# SCH_Vertical-Carousel_2025-01-21.net
KiCad netlist of a schematic drawn in EasyEDA
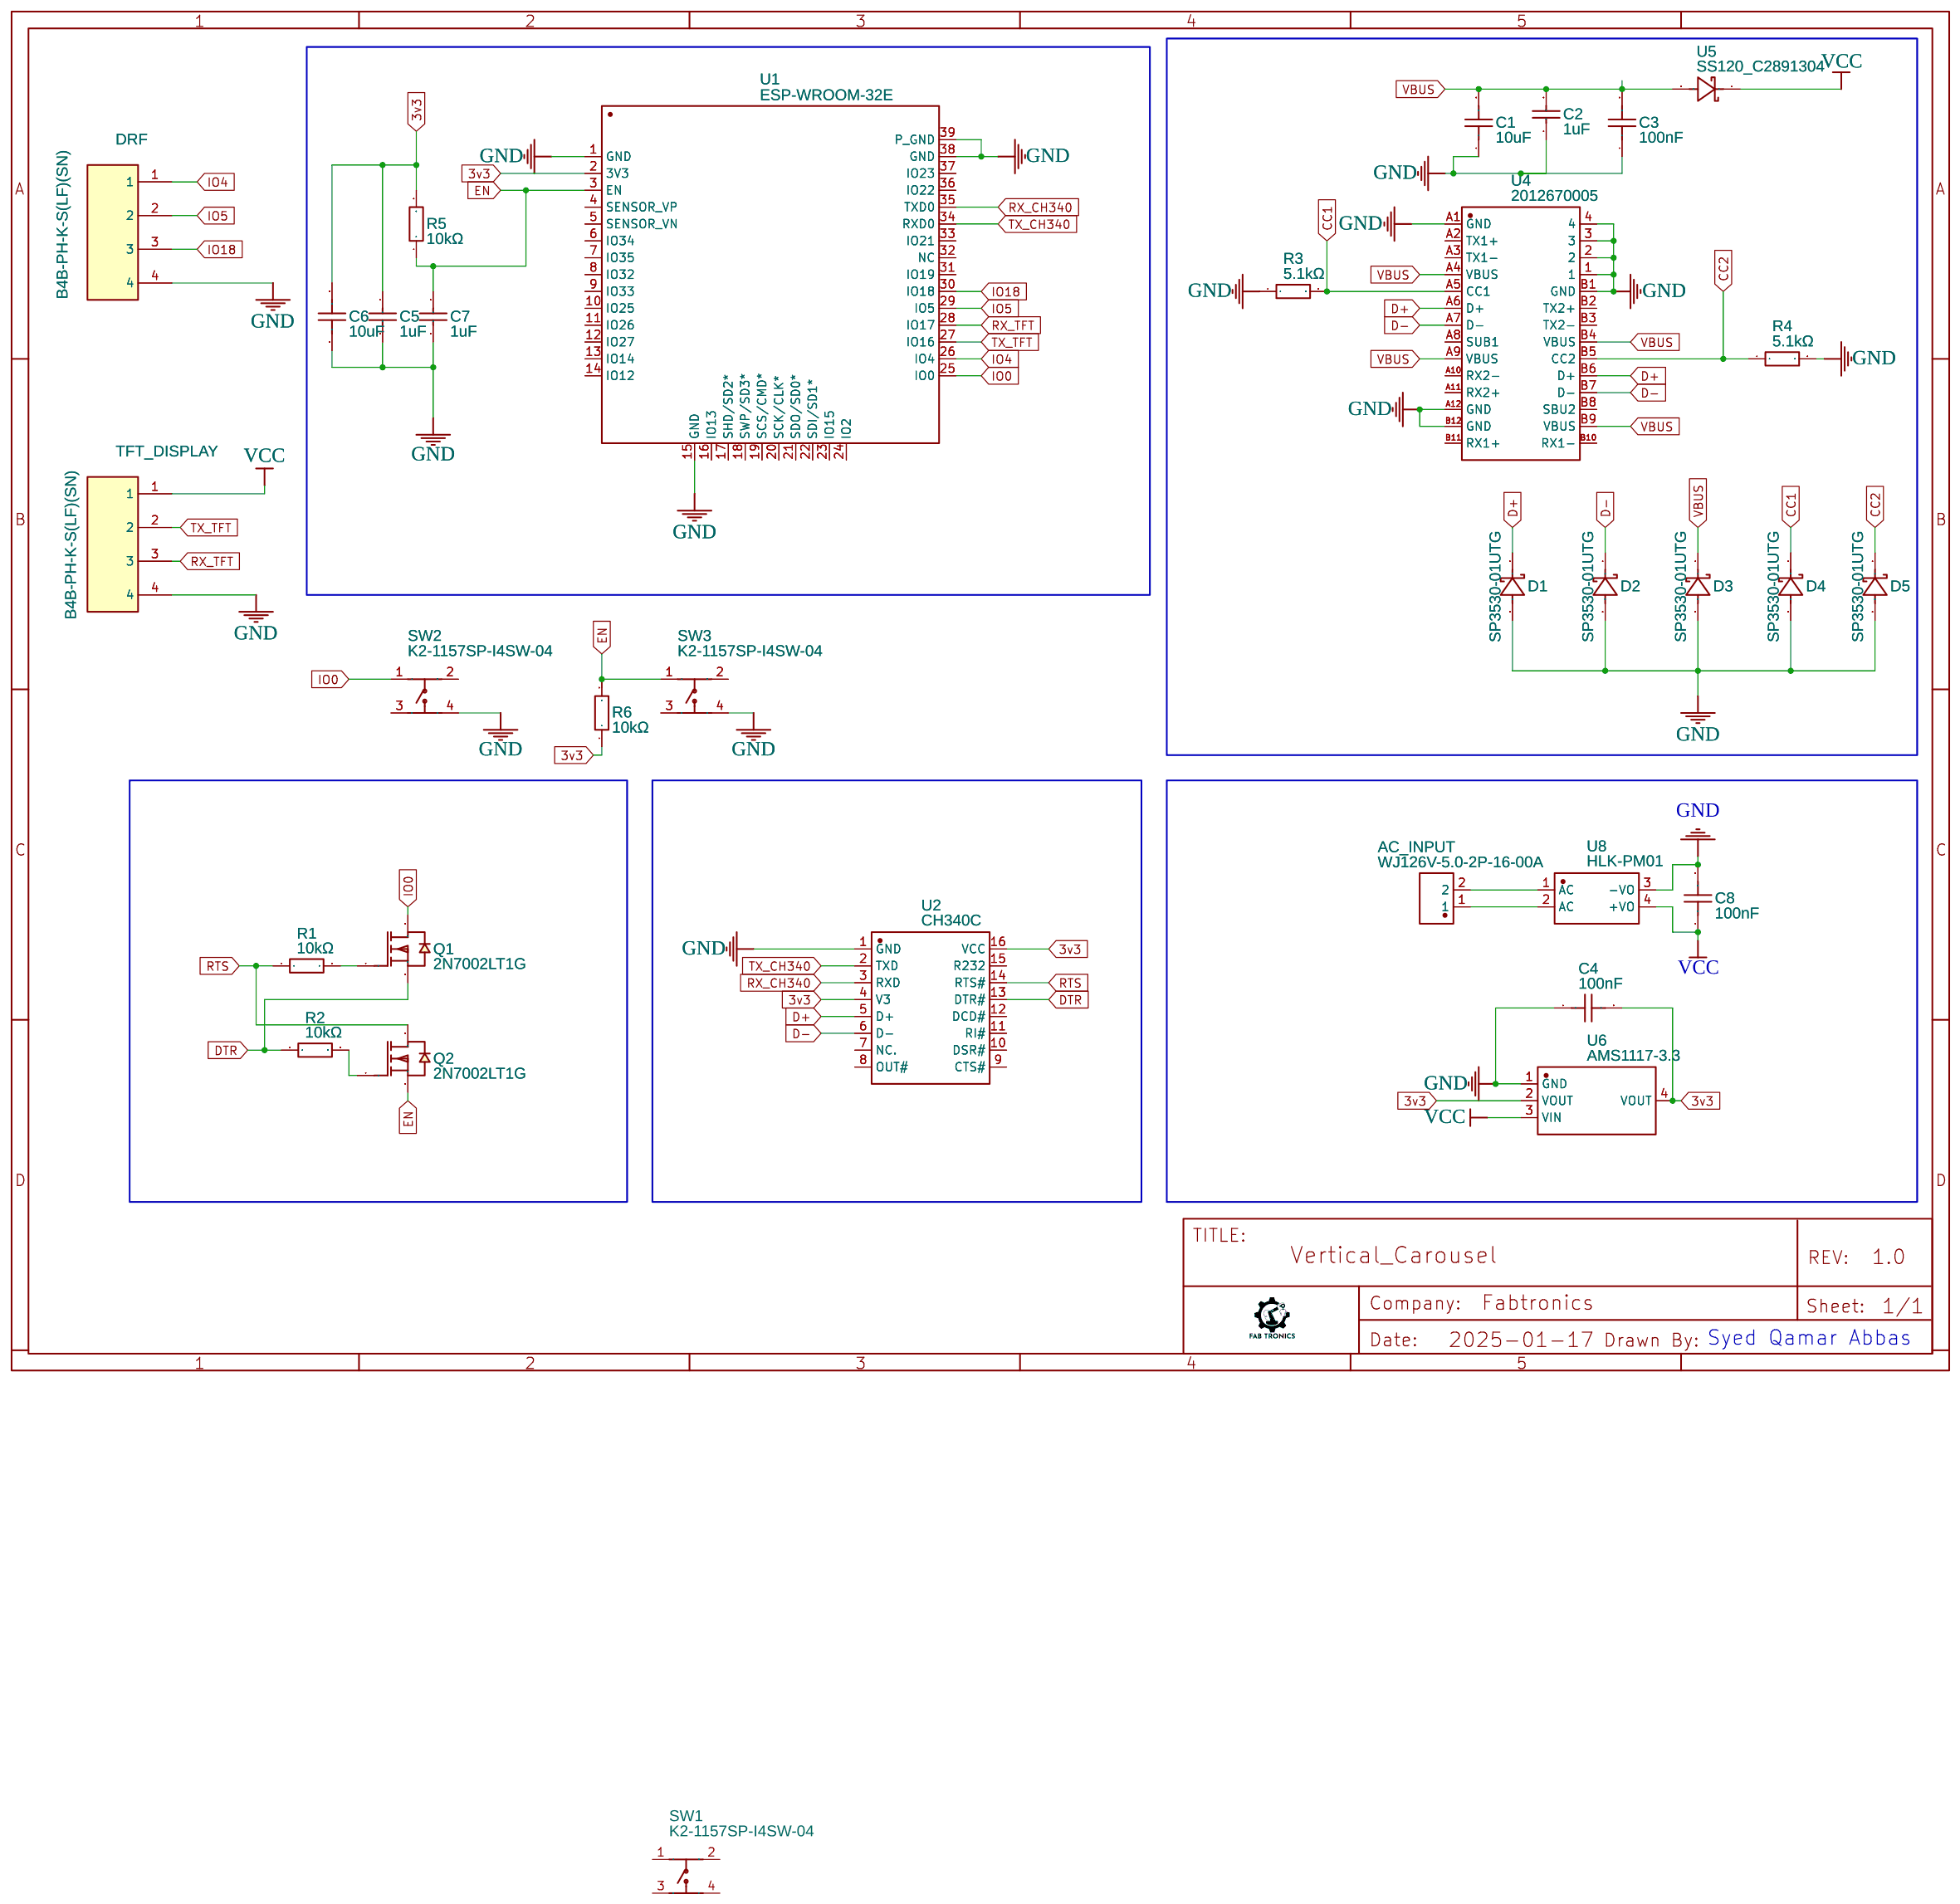
[diagram p0: schematic sheet]

(export (version "E")
  (design (tool "Eeschema 10.0.6"))
  (components
    (comp (ref "AC_INPUT")
      (value "WJ126V-5.0-2P-16-00A")
      (fields (field (name "Manufacturer") "KANGNEX(康奈克斯电气)"))
      (libsource (lib "") (part "WJ126V-5.0-2P-16-00A"))
    )
    (comp (ref "C1")
      (value "10uF")
      (fields
        (field (name "Manufacturer Part") "CL21A106KAYNNNE")
        (field (name "Manufacturer") "SAMSUNG(三星)")
      )
      (libsource (lib "") (part "CL21A106KAYNNNE"))
    )
    (comp (ref "C2")
      (value "1uF")
      (fields
        (field (name "Manufacturer Part") "CL21B105KBFNNNE")
        (field (name "Manufacturer") "SAMSUNG(三星)")
      )
      (libsource (lib "") (part "CL21B105KBFNNNE"))
    )
    (comp (ref "C3")
      (value "100nF")
      (fields
        (field (name "Manufacturer Part") "CC0603KRX7R9BB104")
        (field (name "Manufacturer") "YAGEO(国巨)")
      )
      (libsource (lib "") (part "CC0603KRX7R9BB104"))
    )
    (comp (ref "C4")
      (value "100nF")
      (fields
        (field (name "Manufacturer Part") "CC0603KRX7R9BB104")
        (field (name "Manufacturer") "YAGEO(国巨)")
      )
      (libsource (lib "") (part "CC0603KRX7R9BB104_1"))
    )
    (comp (ref "C5")
      (value "1uF")
      (fields
        (field (name "Manufacturer Part") "CL21B105KBFNNNE")
        (field (name "Manufacturer") "SAMSUNG(三星)")
      )
      (libsource (lib "") (part "CL21B105KBFNNNE"))
    )
    (comp (ref "C6")
      (value "10uF")
      (fields
        (field (name "Manufacturer Part") "CL21A106KAYNNNE")
        (field (name "Manufacturer") "SAMSUNG(三星)")
      )
      (libsource (lib "") (part "CL21A106KAYNNNE"))
    )
    (comp (ref "C7")
      (value "1uF")
      (fields
        (field (name "Manufacturer Part") "CL21B105KBFNNNE")
        (field (name "Manufacturer") "SAMSUNG(三星)")
      )
      (libsource (lib "") (part "CL21B105KBFNNNE"))
    )
    (comp (ref "C8")
      (value "100nF")
      (fields
        (field (name "Manufacturer Part") "CC0603KRX7R9BB104")
        (field (name "Manufacturer") "YAGEO(国巨)")
      )
      (libsource (lib "") (part "CC0603KRX7R9BB104"))
    )
    (comp (ref "D1")
      (value "SP3530-01UTG")
      (fields (field (name "Manufacturer") "Littelfuse(美国力特)"))
      (libsource (lib "") (part "SP3530-01UTG"))
    )
    (comp (ref "D2")
      (value "SP3530-01UTG")
      (fields (field (name "Manufacturer") "Littelfuse(美国力特)"))
      (libsource (lib "") (part "SP3530-01UTG"))
    )
    (comp (ref "D3")
      (value "SP3530-01UTG")
      (fields (field (name "Manufacturer") "Littelfuse(美国力特)"))
      (libsource (lib "") (part "SP3530-01UTG"))
    )
    (comp (ref "D4")
      (value "SP3530-01UTG")
      (fields (field (name "Manufacturer") "Littelfuse(美国力特)"))
      (libsource (lib "") (part "SP3530-01UTG"))
    )
    (comp (ref "D5")
      (value "SP3530-01UTG")
      (fields (field (name "Manufacturer") "Littelfuse(美国力特)"))
      (libsource (lib "") (part "SP3530-01UTG"))
    )
    (comp (ref "DRF")
      (value "B4B-PH-K-S(LF)(SN)")
      (fields (field (name "Manufacturer") "JST"))
      (libsource (lib "") (part "B4B-PH-K-S(LF)(SN)_1"))
    )
    (comp (ref "Q1")
      (value "2N7002LT1G")
      (fields (field (name "Manufacturer") "onsemi(安森美)"))
      (libsource (lib "") (part "2N7002LT1G"))
    )
    (comp (ref "Q2")
      (value "2N7002LT1G")
      (fields (field (name "Manufacturer") "onsemi(安森美)"))
      (libsource (lib "") (part "2N7002LT1G"))
    )
    (comp (ref "R1")
      (value "10kΩ")
      (fields (field (name "Manufacturer Part") "RC0402FR-0710KL") (field (name "Manufacturer") "YAGEO(国巨)"))
      (libsource (lib "") (part "RC0402FR-0710KL_1"))
    )
    (comp (ref "R2")
      (value "10kΩ")
      (fields (field (name "Manufacturer Part") "RC0402FR-0710KL") (field (name "Manufacturer") "YAGEO(国巨)"))
      (libsource (lib "") (part "RC0402FR-0710KL_1"))
    )
    (comp (ref "R3")
      (value "5.1kΩ")
      (fields (field (name "Manufacturer Part") "RS-05K512JT") (field (name "Manufacturer") "FH(风华)"))
      (libsource (lib "") (part "RS-05K512JT"))
    )
    (comp (ref "R4")
      (value "5.1kΩ")
      (fields (field (name "Manufacturer Part") "RS-05K512JT") (field (name "Manufacturer") "FH(风华)"))
      (libsource (lib "") (part "RS-05K512JT"))
    )
    (comp (ref "R5")
      (value "10kΩ")
      (fields (field (name "Manufacturer Part") "RC0402FR-0710KL") (field (name "Manufacturer") "YAGEO(国巨)"))
      (libsource (lib "") (part "RC0402FR-0710KL"))
    )
    (comp (ref "R6")
      (value "10kΩ")
      (fields (field (name "Manufacturer Part") "RC0402FR-0710KL") (field (name "Manufacturer") "YAGEO(国巨)"))
      (libsource (lib "") (part "RC0402FR-0710KL"))
    )
    (comp (ref "SW1")
      (value "K2-1157SP-I4SW-04")
      (fields (field (name "Manufacturer Part") "K2-1157SP-I4SW-01") (field (name "Manufacturer") "韩国韩荣"))
      (libsource (lib "") (part "K2-1157SP-I4SW-04"))
    )
    (comp (ref "SW2")
      (value "K2-1157SP-I4SW-04")
      (fields (field (name "Manufacturer Part") "K2-1157SP-I4SW-01") (field (name "Manufacturer") "韩国韩荣"))
      (libsource (lib "") (part "K2-1157SP-I4SW-04"))
    )
    (comp (ref "SW3")
      (value "K2-1157SP-I4SW-04")
      (fields (field (name "Manufacturer Part") "K2-1157SP-I4SW-01") (field (name "Manufacturer") "韩国韩荣"))
      (libsource (lib "") (part "K2-1157SP-I4SW-04"))
    )
    (comp (ref "TFT_DISPLAY")
      (value "B4B-PH-K-S(LF)(SN)")
      (fields (field (name "Manufacturer") "JST"))
      (libsource (lib "") (part "B4B-PH-K-S(LF)(SN)"))
    )
    (comp (ref "U1")
      (value "ESP-WROOM-32E")
      (fields (field (name "Manufacturer") "DOIT(四博智联)"))
      (libsource (lib "") (part "ESP-WROOM-32E"))
    )
    (comp (ref "U2")
      (value "CH340C")
      (fields (field (name "Manufacturer") "WCH(南京沁恒)"))
      (libsource (lib "") (part "CH340C"))
    )
    (comp (ref "U4")
      (value "2012670005")
      (fields (field (name "Manufacturer") "MOLEX"))
      (libsource (lib "") (part "2012670005"))
    )
    (comp (ref "U5")
      (value "SS120_C2891304")
      (fields (field (name "Manufacturer Part") "SS120") (field (name "Manufacturer") "GOODWORK(固得沃克)"))
      (libsource (lib "") (part "SS120_C2891304"))
    )
    (comp (ref "U6")
      (value "AMS1117-3.3")
      (fields (field (name "Manufacturer") "AMS"))
      (libsource (lib "") (part "AMS1117-3.3"))
    )
    (comp (ref "U8")
      (value "HLK-PM01")
      (fields (field (name "Manufacturer") "HI-LINK(海凌科)"))
      (libsource (lib "") (part "HLK-PM01"))
    )
  )
  (nets
    (net (code "1") (name "3v3") (class "Default")
      (node (ref "C4") (pin "2") (pinfunction "2_2") (pintype "unspecified"))
      (node (ref "C5") (pin "2") (pinfunction "2_2") (pintype "input"))
      (node (ref "C6") (pin "2") (pinfunction "2_2") (pintype "unspecified"))
      (node (ref "R5") (pin "2") (pinfunction "2_2") (pintype "input"))
      (node (ref "R6") (pin "1") (pinfunction "1_1") (pintype "input"))
      (node (ref "U1") (pin "2") (pinfunction "3V3_2") (pintype "unspecified"))
      (node (ref "U2") (pin "16") (pinfunction "VCC_16") (pintype "unspecified"))
      (node (ref "U2") (pin "4") (pinfunction "V3_4") (pintype "unspecified"))
      (node (ref "U6") (pin "2") (pinfunction "VOUT_2") (pintype "unspecified"))
      (node (ref "U6") (pin "4") (pinfunction "VOUT_4") (pintype "unspecified"))
    )
    (net (code "2") (name "CC1") (class "Default")
      (node (ref "D4") (pin "1") (pinfunction "1_1") (pintype "unspecified"))
      (node (ref "R3") (pin "2") (pinfunction "2_2") (pintype "unspecified"))
      (node (ref "U4") (pin "A5") (pinfunction "CC1_A5") (pintype "unspecified"))
    )
    (net (code "3") (name "CC2") (class "Default")
      (node (ref "D5") (pin "1") (pinfunction "1_1") (pintype "unspecified"))
      (node (ref "R4") (pin "1") (pinfunction "1_1") (pintype "unspecified"))
      (node (ref "U4") (pin "B5") (pinfunction "CC2_B5") (pintype "unspecified"))
    )
    (net (code "4") (name "D+") (class "Default")
      (node (ref "D1") (pin "1") (pinfunction "1_1") (pintype "unspecified"))
      (node (ref "U2") (pin "5") (pinfunction "D+_5") (pintype "unspecified"))
      (node (ref "U4") (pin "A6") (pinfunction "D+_A6") (pintype "unspecified"))
      (node (ref "U4") (pin "B6") (pinfunction "D+_B6") (pintype "unspecified"))
    )
    (net (code "5") (name "D-") (class "Default")
      (node (ref "D2") (pin "1") (pinfunction "1_1") (pintype "unspecified"))
      (node (ref "U2") (pin "6") (pinfunction "D-_6") (pintype "unspecified"))
      (node (ref "U4") (pin "A7") (pinfunction "D-_A7") (pintype "unspecified"))
      (node (ref "U4") (pin "B7") (pinfunction "D-_B7") (pintype "unspecified"))
    )
    (net (code "6") (name "DTR") (class "Default")
      (node (ref "Q1") (pin "2") (pinfunction "S_2") (pintype "unspecified"))
      (node (ref "R2") (pin "1") (pinfunction "1_1") (pintype "input"))
      (node (ref "U2") (pin "13") (pinfunction "DTR#_13") (pintype "unspecified"))
    )
    (net (code "7") (name "EN") (class "Default")
      (node (ref "C7") (pin "2") (pinfunction "2_2") (pintype "input"))
      (node (ref "Q2") (pin "2") (pinfunction "S_2") (pintype "unspecified"))
      (node (ref "R5") (pin "1") (pinfunction "1_1") (pintype "input"))
      (node (ref "R6") (pin "2") (pinfunction "2_2") (pintype "input"))
      (node (ref "SW3") (pin "1") (pinfunction "1_1") (pintype "unspecified"))
      (node (ref "U1") (pin "3") (pinfunction "EN_3") (pintype "unspecified"))
    )
    (net (code "8") (name "GND") (class "Default")
      (node (ref "C1") (pin "1") (pinfunction "1_1") (pintype "unspecified"))
      (node (ref "C2") (pin "1") (pinfunction "1_1") (pintype "input"))
      (node (ref "C3") (pin "1") (pinfunction "1_1") (pintype "unspecified"))
      (node (ref "C4") (pin "1") (pinfunction "1_1") (pintype "unspecified"))
      (node (ref "C5") (pin "1") (pinfunction "1_1") (pintype "input"))
      (node (ref "C6") (pin "1") (pinfunction "1_1") (pintype "unspecified"))
      (node (ref "C7") (pin "1") (pinfunction "1_1") (pintype "input"))
      (node (ref "C8") (pin "2") (pinfunction "2_2") (pintype "unspecified"))
      (node (ref "D1") (pin "2") (pinfunction "2_2") (pintype "unspecified"))
      (node (ref "D2") (pin "2") (pinfunction "2_2") (pintype "unspecified"))
      (node (ref "D3") (pin "2") (pinfunction "2_2") (pintype "unspecified"))
      (node (ref "D4") (pin "2") (pinfunction "2_2") (pintype "unspecified"))
      (node (ref "D5") (pin "2") (pinfunction "2_2") (pintype "unspecified"))
      (node (ref "DRF") (pin "4") (pinfunction "4_4") (pintype "input"))
      (node (ref "R3") (pin "1") (pinfunction "1_1") (pintype "unspecified"))
      (node (ref "R4") (pin "2") (pinfunction "2_2") (pintype "unspecified"))
      (node (ref "SW2") (pin "4") (pinfunction "4_4") (pintype "unspecified"))
      (node (ref "SW3") (pin "4") (pinfunction "4_4") (pintype "unspecified"))
      (node (ref "TFT_DISPLAY") (pin "4") (pinfunction "4_4") (pintype "input"))
      (node (ref "U1") (pin "1") (pinfunction "GND_1") (pintype "unspecified"))
      (node (ref "U1") (pin "15") (pinfunction "GND_15") (pintype "unspecified"))
      (node (ref "U1") (pin "38") (pinfunction "GND_38") (pintype "unspecified"))
      (node (ref "U1") (pin "39") (pinfunction "P_GND_39") (pintype "unspecified"))
      (node (ref "U2") (pin "1") (pinfunction "GND_1") (pintype "unspecified"))
      (node (ref "U4") (pin "1") (pinfunction "1_1") (pintype "unspecified"))
      (node (ref "U4") (pin "2") (pinfunction "2_2") (pintype "unspecified"))
      (node (ref "U4") (pin "3") (pinfunction "3_3") (pintype "unspecified"))
      (node (ref "U4") (pin "4") (pinfunction "4_4") (pintype "unspecified"))
      (node (ref "U4") (pin "A1") (pinfunction "GND_A1") (pintype "unspecified"))
      (node (ref "U4") (pin "A12") (pinfunction "GND_A12") (pintype "unspecified"))
      (node (ref "U4") (pin "B1") (pinfunction "GND_B1") (pintype "unspecified"))
      (node (ref "U4") (pin "B12") (pinfunction "GND_B12") (pintype "unspecified"))
      (node (ref "U6") (pin "1") (pinfunction "GND_1") (pintype "unspecified"))
      (node (ref "U8") (pin "3") (pinfunction "-VO_3") (pintype "unspecified"))
    )
    (net (code "9") (name "IO0") (class "Default")
      (node (ref "Q1") (pin "3") (pinfunction "D_3") (pintype "unspecified"))
      (node (ref "SW2") (pin "1") (pinfunction "1_1") (pintype "unspecified"))
      (node (ref "U1") (pin "25") (pinfunction "IO0_25") (pintype "unspecified"))
    )
    (net (code "10") (name "IO4") (class "Default")
      (node (ref "DRF") (pin "1") (pinfunction "1_1") (pintype "input"))
      (node (ref "U1") (pin "26") (pinfunction "IO4_26") (pintype "unspecified"))
    )
    (net (code "11") (name "IO5") (class "Default")
      (node (ref "DRF") (pin "2") (pinfunction "2_2") (pintype "input"))
      (node (ref "U1") (pin "29") (pinfunction "IO5_29") (pintype "unspecified"))
    )
    (net (code "12") (name "IO18") (class "Default")
      (node (ref "DRF") (pin "3") (pinfunction "3_3") (pintype "input"))
      (node (ref "U1") (pin "30") (pinfunction "IO18_30") (pintype "unspecified"))
    )
    (net (code "13") (name "Net-(AC_INPUT-Pad1)") (class "Default")
      (node (ref "AC_INPUT") (pin "1") (pinfunction "1_1") (pintype "unspecified"))
      (node (ref "U8") (pin "2") (pinfunction "AC_2") (pintype "unspecified"))
    )
    (net (code "14") (name "Net-(AC_INPUT-Pad2)") (class "Default")
      (node (ref "AC_INPUT") (pin "2") (pinfunction "2_2") (pintype "unspecified"))
      (node (ref "U8") (pin "1") (pinfunction "AC_1") (pintype "unspecified"))
    )
    (net (code "15") (name "Net-(Q1-G)") (class "Default")
      (node (ref "Q1") (pin "1") (pinfunction "G_1") (pintype "unspecified"))
      (node (ref "R1") (pin "2") (pinfunction "2_2") (pintype "input"))
    )
    (net (code "16") (name "Net-(Q2-G)") (class "Default")
      (node (ref "Q2") (pin "1") (pinfunction "G_1") (pintype "unspecified"))
      (node (ref "R2") (pin "2") (pinfunction "2_2") (pintype "input"))
    )
    (net (code "17") (name "RTS") (class "Default")
      (node (ref "Q2") (pin "3") (pinfunction "D_3") (pintype "unspecified"))
      (node (ref "R1") (pin "1") (pinfunction "1_1") (pintype "input"))
      (node (ref "U2") (pin "14") (pinfunction "RTS#_14") (pintype "unspecified"))
    )
    (net (code "18") (name "RX_CH340") (class "Default")
      (node (ref "U1") (pin "35") (pinfunction "TXD0_35") (pintype "unspecified"))
      (node (ref "U2") (pin "3") (pinfunction "RXD_3") (pintype "unspecified"))
    )
    (net (code "19") (name "RX_TFT") (class "Default")
      (node (ref "TFT_DISPLAY") (pin "3") (pinfunction "3_3") (pintype "input"))
      (node (ref "U1") (pin "28") (pinfunction "IO17_28") (pintype "unspecified"))
    )
    (net (code "20") (name "TX_CH340") (class "Default")
      (node (ref "U1") (pin "34") (pinfunction "RXD0_34") (pintype "unspecified"))
      (node (ref "U2") (pin "2") (pinfunction "TXD_2") (pintype "unspecified"))
    )
    (net (code "21") (name "TX_TFT") (class "Default")
      (node (ref "TFT_DISPLAY") (pin "2") (pinfunction "2_2") (pintype "input"))
      (node (ref "U1") (pin "27") (pinfunction "IO16_27") (pintype "unspecified"))
    )
    (net (code "22") (name "VBUS") (class "Default")
      (node (ref "C1") (pin "2") (pinfunction "2_2") (pintype "unspecified"))
      (node (ref "C2") (pin "2") (pinfunction "2_2") (pintype "input"))
      (node (ref "C3") (pin "2") (pinfunction "2_2") (pintype "unspecified"))
      (node (ref "D3") (pin "1") (pinfunction "1_1") (pintype "unspecified"))
      (node (ref "U4") (pin "A4") (pinfunction "VBUS_A4") (pintype "unspecified"))
      (node (ref "U4") (pin "A9") (pinfunction "VBUS_A9") (pintype "unspecified"))
      (node (ref "U4") (pin "B4") (pinfunction "VBUS_B4") (pintype "unspecified"))
      (node (ref "U4") (pin "B9") (pinfunction "VBUS_B9") (pintype "unspecified"))
      (node (ref "U5") (pin "2") (pinfunction "A_2") (pintype "unspecified"))
    )
    (net (code "23") (name "VCC") (class "Default")
      (node (ref "C8") (pin "1") (pinfunction "1_1") (pintype "unspecified"))
      (node (ref "TFT_DISPLAY") (pin "1") (pinfunction "1_1") (pintype "input"))
      (node (ref "U5") (pin "1") (pinfunction "K_1") (pintype "unspecified"))
      (node (ref "U6") (pin "3") (pinfunction "VIN_3") (pintype "unspecified"))
      (node (ref "U8") (pin "4") (pinfunction "+VO_4") (pintype "unspecified"))
    )
    (net (code "24") (name "unconnected-(SW1-Pad1)") (class "Default")
      (node (ref "SW1") (pin "1") (pinfunction "1_1") (pintype "unspecified"))
    )
    (net (code "25") (name "unconnected-(SW1-Pad2)") (class "Default")
      (node (ref "SW1") (pin "2") (pinfunction "2_2") (pintype "unspecified"))
    )
    (net (code "26") (name "unconnected-(SW1-Pad3)") (class "Default")
      (node (ref "SW1") (pin "3") (pinfunction "3_3") (pintype "unspecified"))
    )
    (net (code "27") (name "unconnected-(SW1-Pad4)") (class "Default")
      (node (ref "SW1") (pin "4") (pinfunction "4_4") (pintype "unspecified"))
    )
    (net (code "28") (name "unconnected-(SW2-Pad2)") (class "Default")
      (node (ref "SW2") (pin "2") (pinfunction "2_2") (pintype "unspecified"))
    )
    (net (code "29") (name "unconnected-(SW2-Pad3)") (class "Default")
      (node (ref "SW2") (pin "3") (pinfunction "3_3") (pintype "unspecified"))
    )
    (net (code "30") (name "unconnected-(SW3-Pad2)") (class "Default")
      (node (ref "SW3") (pin "2") (pinfunction "2_2") (pintype "unspecified"))
    )
    (net (code "31") (name "unconnected-(SW3-Pad3)") (class "Default")
      (node (ref "SW3") (pin "3") (pinfunction "3_3") (pintype "unspecified"))
    )
    (net (code "32") (name "unconnected-(U1-IO2-Pad24)") (class "Default")
      (node (ref "U1") (pin "24") (pinfunction "IO2_24") (pintype "unspecified"))
    )
    (net (code "33") (name "unconnected-(U1-IO12-Pad14)") (class "Default")
      (node (ref "U1") (pin "14") (pinfunction "IO12_14") (pintype "unspecified"))
    )
    (net (code "34") (name "unconnected-(U1-IO13-Pad16)") (class "Default")
      (node (ref "U1") (pin "16") (pinfunction "IO13_16") (pintype "unspecified"))
    )
    (net (code "35") (name "unconnected-(U1-IO14-Pad13)") (class "Default")
      (node (ref "U1") (pin "13") (pinfunction "IO14_13") (pintype "unspecified"))
    )
    (net (code "36") (name "unconnected-(U1-IO15-Pad23)") (class "Default")
      (node (ref "U1") (pin "23") (pinfunction "IO15_23") (pintype "unspecified"))
    )
    (net (code "37") (name "unconnected-(U1-IO19-Pad31)") (class "Default")
      (node (ref "U1") (pin "31") (pinfunction "IO19_31") (pintype "unspecified"))
    )
    (net (code "38") (name "unconnected-(U1-IO21-Pad33)") (class "Default")
      (node (ref "U1") (pin "33") (pinfunction "IO21_33") (pintype "unspecified"))
    )
    (net (code "39") (name "unconnected-(U1-IO22-Pad36)") (class "Default")
      (node (ref "U1") (pin "36") (pinfunction "IO22_36") (pintype "unspecified"))
    )
    (net (code "40") (name "unconnected-(U1-IO23-Pad37)") (class "Default")
      (node (ref "U1") (pin "37") (pinfunction "IO23_37") (pintype "unspecified"))
    )
    (net (code "41") (name "unconnected-(U1-IO25-Pad10)") (class "Default")
      (node (ref "U1") (pin "10") (pinfunction "IO25_10") (pintype "unspecified"))
    )
    (net (code "42") (name "unconnected-(U1-IO26-Pad11)") (class "Default")
      (node (ref "U1") (pin "11") (pinfunction "IO26_11") (pintype "unspecified"))
    )
    (net (code "43") (name "unconnected-(U1-IO27-Pad12)") (class "Default")
      (node (ref "U1") (pin "12") (pinfunction "IO27_12") (pintype "unspecified"))
    )
    (net (code "44") (name "unconnected-(U1-IO32-Pad8)") (class "Default")
      (node (ref "U1") (pin "8") (pinfunction "IO32_8") (pintype "unspecified"))
    )
    (net (code "45") (name "unconnected-(U1-IO33-Pad9)") (class "Default")
      (node (ref "U1") (pin "9") (pinfunction "IO33_9") (pintype "unspecified"))
    )
    (net (code "46") (name "unconnected-(U1-IO34-Pad6)") (class "Default")
      (node (ref "U1") (pin "6") (pinfunction "IO34_6") (pintype "unspecified"))
    )
    (net (code "47") (name "unconnected-(U1-IO35-Pad7)") (class "Default")
      (node (ref "U1") (pin "7") (pinfunction "IO35_7") (pintype "unspecified"))
    )
    (net (code "48") (name "unconnected-(U1-NC-Pad32)") (class "Default")
      (node (ref "U1") (pin "32") (pinfunction "NC_32") (pintype "unspecified"))
    )
    (net (code "49") (name "unconnected-(U1-SCK{slash}CLK*-Pad20)") (class "Default")
      (node (ref "U1") (pin "20") (pinfunction "SCK/CLK*_20") (pintype "unspecified"))
    )
    (net (code "50") (name "unconnected-(U1-SCS{slash}CMD*-Pad19)") (class "Default")
      (node (ref "U1") (pin "19") (pinfunction "SCS/CMD*_19") (pintype "unspecified"))
    )
    (net (code "51") (name "unconnected-(U1-SDI{slash}SD1*-Pad22)") (class "Default")
      (node (ref "U1") (pin "22") (pinfunction "SDI/SD1*_22") (pintype "unspecified"))
    )
    (net (code "52") (name "unconnected-(U1-SDO{slash}SD0*-Pad21)") (class "Default")
      (node (ref "U1") (pin "21") (pinfunction "SDO/SD0*_21") (pintype "unspecified"))
    )
    (net (code "53") (name "unconnected-(U1-SENSOR_VN-Pad5)") (class "Default")
      (node (ref "U1") (pin "5") (pinfunction "SENSOR_VN_5") (pintype "unspecified"))
    )
    (net (code "54") (name "unconnected-(U1-SENSOR_VP-Pad4)") (class "Default")
      (node (ref "U1") (pin "4") (pinfunction "SENSOR_VP_4") (pintype "unspecified"))
    )
    (net (code "55") (name "unconnected-(U1-SHD{slash}SD2*-Pad17)") (class "Default")
      (node (ref "U1") (pin "17") (pinfunction "SHD/SD2*_17") (pintype "unspecified"))
    )
    (net (code "56") (name "unconnected-(U1-SWP{slash}SD3*-Pad18)") (class "Default")
      (node (ref "U1") (pin "18") (pinfunction "SWP/SD3*_18") (pintype "unspecified"))
    )
    (net (code "57") (name "unconnected-(U2-CTS#-Pad9)") (class "Default")
      (node (ref "U2") (pin "9") (pinfunction "CTS#_9") (pintype "unspecified"))
    )
    (net (code "58") (name "unconnected-(U2-DCD#-Pad12)") (class "Default")
      (node (ref "U2") (pin "12") (pinfunction "DCD#_12") (pintype "unspecified"))
    )
    (net (code "59") (name "unconnected-(U2-DSR#-Pad10)") (class "Default")
      (node (ref "U2") (pin "10") (pinfunction "DSR#_10") (pintype "unspecified"))
    )
    (net (code "60") (name "unconnected-(U2-NC.-Pad7)") (class "Default")
      (node (ref "U2") (pin "7") (pinfunction "NC._7") (pintype "unspecified"))
    )
    (net (code "61") (name "unconnected-(U2-OUT#-Pad8)") (class "Default")
      (node (ref "U2") (pin "8") (pinfunction "OUT#_8") (pintype "unspecified"))
    )
    (net (code "62") (name "unconnected-(U2-R232-Pad15)") (class "Default")
      (node (ref "U2") (pin "15") (pinfunction "R232_15") (pintype "unspecified"))
    )
    (net (code "63") (name "unconnected-(U2-RI#-Pad11)") (class "Default")
      (node (ref "U2") (pin "11") (pinfunction "RI#_11") (pintype "unspecified"))
    )
    (net (code "64") (name "unconnected-(U4-RX1+-PadB11)") (class "Default")
      (node (ref "U4") (pin "B11") (pinfunction "RX1+_B11") (pintype "unspecified"))
    )
    (net (code "65") (name "unconnected-(U4-RX1--PadB10)") (class "Default")
      (node (ref "U4") (pin "B10") (pinfunction "RX1-_B10") (pintype "unspecified"))
    )
    (net (code "66") (name "unconnected-(U4-RX2+-PadA11)") (class "Default")
      (node (ref "U4") (pin "A11") (pinfunction "RX2+_A11") (pintype "unspecified"))
    )
    (net (code "67") (name "unconnected-(U4-RX2--PadA10)") (class "Default")
      (node (ref "U4") (pin "A10") (pinfunction "RX2-_A10") (pintype "unspecified"))
    )
    (net (code "68") (name "unconnected-(U4-SBU2-PadB8)") (class "Default")
      (node (ref "U4") (pin "B8") (pinfunction "SBU2_B8") (pintype "unspecified"))
    )
    (net (code "69") (name "unconnected-(U4-SUB1-PadA8)") (class "Default")
      (node (ref "U4") (pin "A8") (pinfunction "SUB1_A8") (pintype "unspecified"))
    )
    (net (code "70") (name "unconnected-(U4-TX1+-PadA2)") (class "Default")
      (node (ref "U4") (pin "A2") (pinfunction "TX1+_A2") (pintype "unspecified"))
    )
    (net (code "71") (name "unconnected-(U4-TX1--PadA3)") (class "Default")
      (node (ref "U4") (pin "A3") (pinfunction "TX1-_A3") (pintype "unspecified"))
    )
    (net (code "72") (name "unconnected-(U4-TX2+-PadB2)") (class "Default")
      (node (ref "U4") (pin "B2") (pinfunction "TX2+_B2") (pintype "unspecified"))
    )
    (net (code "73") (name "unconnected-(U4-TX2--PadB3)") (class "Default")
      (node (ref "U4") (pin "B3") (pinfunction "TX2-_B3") (pintype "unspecified"))
    )
  )
)
